# DIO_2.net
KiCad netlist of a schematic drawn in Altium Designer
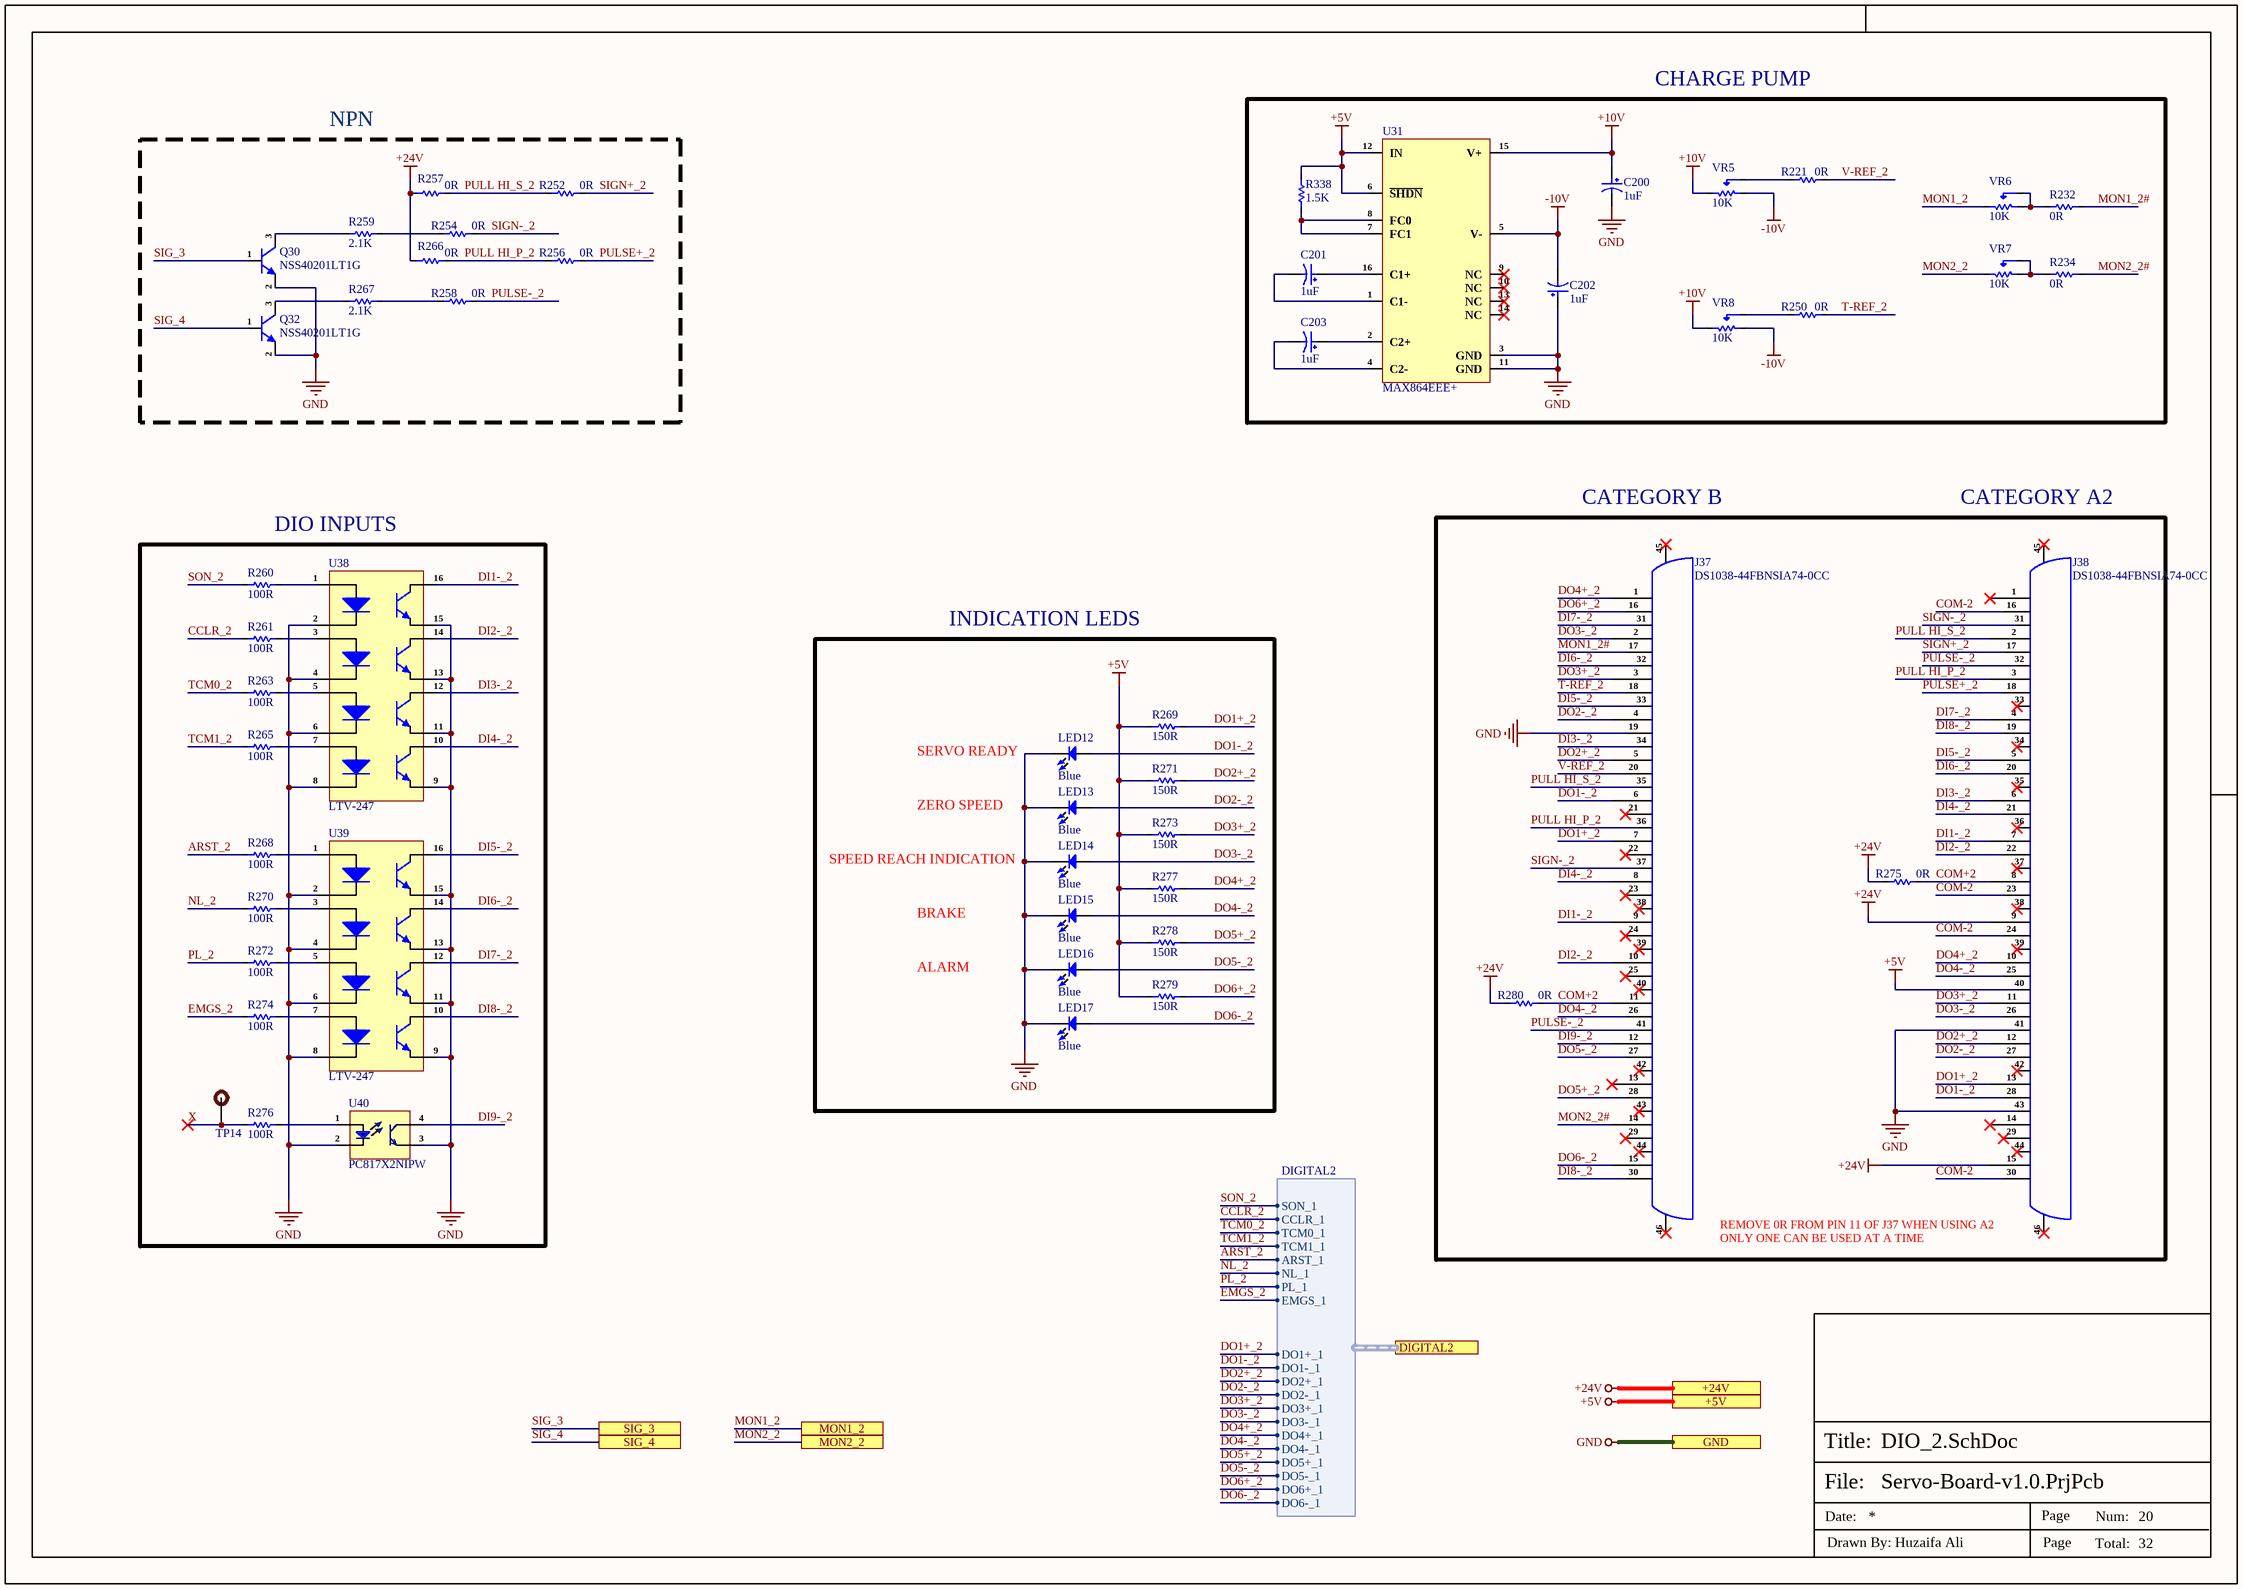
[diagram p0: DIO_2.SchDoc]

(export (version "E")
  (design (tool "Eeschema 10.0.6"))
  (components
    (comp (ref "C200")
      (value "1uF")
      (footprint "RVT1H1R0M0405")
      (description "1uF 50V 8mA@120Hz ±20% SMD,D4xL5.4mm Aluminum Electrolytic Capacitors - SMD ROHS")
      (fields (field (name "LCSC PART NUMBER") "C72491") (field (name "MANUFACTURER") "Roqang"))
      (libsource (lib "") (part "RVT1H1R0M0405_2"))
    )
    (comp (ref "C201")
      (value "1uF")
      (footprint "RVT1H1R0M0405")
      (description "1uF 50V 8mA@120Hz ±20% SMD,D4xL5.4mm Aluminum Electrolytic Capacitors - SMD ROHS")
      (fields (field (name "LCSC PART NUMBER") "C72491") (field (name "MANUFACTURER") "Roqang"))
      (libsource (lib "eSpark Libraries") (part "RVT1H1R0M0405"))
    )
    (comp (ref "C202")
      (value "1uF")
      (footprint "RVT1H1R0M0405")
      (description "1uF 50V 8mA@120Hz ±20% SMD,D4xL5.4mm Aluminum Electrolytic Capacitors - SMD ROHS")
      (fields (field (name "LCSC PART NUMBER") "C72491") (field (name "MANUFACTURER") "Roqang"))
      (libsource (lib "") (part "RVT1H1R0M0405_1"))
    )
    (comp (ref "C203")
      (value "1uF")
      (footprint "RVT1H1R0M0405")
      (description "1uF 50V 8mA@120Hz ±20% SMD,D4xL5.4mm Aluminum Electrolytic Capacitors - SMD ROHS")
      (fields (field (name "LCSC PART NUMBER") "C72491") (field (name "MANUFACTURER") "Roqang"))
      (libsource (lib "eSpark Libraries") (part "RVT1H1R0M0405"))
    )
    (comp (ref "J37")
      (value "DS1038-44FBNSIA74-0CC")
      (footprint "DS1038-44FBNSIA74-0CC")
      (description "44P Female D-Sub Right-Angle 3 1.5A -40℃~+105℃ Push-Pull D-Sub / VGA connector ROHS")
      (fields (field (name "MANUFACTURER") "CONNFLY Elec") (field (name "LCSC PART NUMBER") "C77844"))
      (libsource (lib "eSpark Libraries") (part "DS1038-44FBNSIA74-0CC"))
    )
    (comp (ref "J38")
      (value "DS1038-44FBNSIA74-0CC")
      (footprint "DS1038-44FBNSIA74-0CC")
      (description "44P Female D-Sub Right-Angle 3 1.5A -40℃~+105℃ Push-Pull D-Sub / VGA connector ROHS")
      (fields (field (name "MANUFACTURER") "CONNFLY Elec") (field (name "LCSC PART NUMBER") "C77844"))
      (libsource (lib "eSpark Libraries") (part "DS1038-44FBNSIA74-0CC"))
    )
    (comp (ref "LED12")
      (value "Blue")
      (footprint "LED-0603")
      (description "blue 0603 Light Emitting Diodes (LED) ROHS")
      (fields
        (field (name "MANUFACTURER") "Foshan NationStar Optoelectronics")
        (field (name "MANUFACTURER PART NUMBER") "NCD0603B3")
      )
      (libsource (lib "eSpark Libraries") (part "NCD0603B3"))
    )
    (comp (ref "LED13")
      (value "Blue")
      (footprint "LED-0603")
      (description "blue 0603 Light Emitting Diodes (LED) ROHS")
      (fields
        (field (name "MANUFACTURER") "Foshan NationStar Optoelectronics")
        (field (name "MANUFACTURER PART NUMBER") "NCD0603B3")
      )
      (libsource (lib "eSpark Libraries") (part "NCD0603B3"))
    )
    (comp (ref "LED14")
      (value "Blue")
      (footprint "LED-0603")
      (description "blue 0603 Light Emitting Diodes (LED) ROHS")
      (fields
        (field (name "MANUFACTURER") "Foshan NationStar Optoelectronics")
        (field (name "MANUFACTURER PART NUMBER") "NCD0603B3")
      )
      (libsource (lib "eSpark Libraries") (part "NCD0603B3"))
    )
    (comp (ref "LED15")
      (value "Blue")
      (footprint "LED-0603")
      (description "blue 0603 Light Emitting Diodes (LED) ROHS")
      (fields
        (field (name "MANUFACTURER") "Foshan NationStar Optoelectronics")
        (field (name "MANUFACTURER PART NUMBER") "NCD0603B3")
      )
      (libsource (lib "eSpark Libraries") (part "NCD0603B3"))
    )
    (comp (ref "LED16")
      (value "Blue")
      (footprint "LED-0603")
      (description "blue 0603 Light Emitting Diodes (LED) ROHS")
      (fields
        (field (name "MANUFACTURER") "Foshan NationStar Optoelectronics")
        (field (name "MANUFACTURER PART NUMBER") "NCD0603B3")
      )
      (libsource (lib "eSpark Libraries") (part "NCD0603B3"))
    )
    (comp (ref "LED17")
      (value "Blue")
      (footprint "LED-0603")
      (description "blue 0603 Light Emitting Diodes (LED) ROHS")
      (fields
        (field (name "MANUFACTURER") "Foshan NationStar Optoelectronics")
        (field (name "MANUFACTURER PART NUMBER") "NCD0603B3")
      )
      (libsource (lib "eSpark Libraries") (part "NCD0603B3"))
    )
    (comp (ref "Q30")
      (value "NSS40201LT1G")
      (footprint "SOT-23")
      (description "TRANS NPN 40V 2A SOT23-3")
      (fields (field (name "MANUFACTURER") "ON Semiconductor") (field (name "LCSC PART NUMBER") "C145175"))
      (libsource (lib "eSpark Libraries") (part "NSS40201LT1G"))
    )
    (comp (ref "Q32")
      (value "NSS40201LT1G")
      (footprint "SOT-23")
      (description "TRANS NPN 40V 2A SOT23-3")
      (fields (field (name "MANUFACTURER") "ON Semiconductor") (field (name "LCSC PART NUMBER") "C145175"))
      (libsource (lib "eSpark Libraries") (part "NSS40201LT1G"))
    )
    (comp (ref "R221")
      (value "0R")
      (footprint "Res-0402")
      (description "RES 0 OHM JUMPER 1/16W 0402")
      (fields
        (field (name "MANUFACTURER") "Yageo")
        (field (name "MANUFACTURER PART NUMBER") "RC0402FR-070RL")
      )
      (libsource (lib "eSpark Libraries") (part "RC0402FR-070RL"))
    )
    (comp (ref "R232")
      (value "0R")
      (footprint "Res-0402")
      (description "RES 0 OHM JUMPER 1/16W 0402")
      (fields
        (field (name "MANUFACTURER") "Yageo")
        (field (name "MANUFACTURER PART NUMBER") "RC0402FR-070RL")
      )
      (libsource (lib "eSpark Libraries") (part "RC0402FR-070RL"))
    )
    (comp (ref "R234")
      (value "0R")
      (footprint "Res-0402")
      (description "RES 0 OHM JUMPER 1/16W 0402")
      (fields
        (field (name "MANUFACTURER") "Yageo")
        (field (name "MANUFACTURER PART NUMBER") "RC0402FR-070RL")
      )
      (libsource (lib "eSpark Libraries") (part "RC0402FR-070RL"))
    )
    (comp (ref "R250")
      (value "0R")
      (footprint "Res-0402")
      (description "RES 0 OHM JUMPER 1/16W 0402")
      (fields
        (field (name "MANUFACTURER") "Yageo")
        (field (name "MANUFACTURER PART NUMBER") "RC0402FR-070RL")
      )
      (libsource (lib "eSpark Libraries") (part "RC0402FR-070RL"))
    )
    (comp (ref "R252")
      (value "0R")
      (footprint "Res-0603")
      (description "RES 0 OHM JUMPER 1/10W 0603")
      (fields
        (field (name "MANUFACTURER") "Yageo")
        (field (name "MANUFACTURER PART NUMBER") "RC0603JR-070RL")
      )
      (libsource (lib "eSpark Libraries") (part "RC0603JR-070RL"))
    )
    (comp (ref "R254")
      (value "0R")
      (footprint "Res-0603")
      (description "RES 0 OHM JUMPER 1/10W 0603")
      (fields
        (field (name "MANUFACTURER") "Yageo")
        (field (name "MANUFACTURER PART NUMBER") "RC0603JR-070RL")
      )
      (libsource (lib "eSpark Libraries") (part "RC0603JR-070RL"))
    )
    (comp (ref "R256")
      (value "0R")
      (footprint "Res-0603")
      (description "RES 0 OHM JUMPER 1/10W 0603")
      (fields
        (field (name "MANUFACTURER") "Yageo")
        (field (name "MANUFACTURER PART NUMBER") "RC0603JR-070RL")
      )
      (libsource (lib "eSpark Libraries") (part "RC0603JR-070RL"))
    )
    (comp (ref "R257")
      (value "0R")
      (footprint "Res-0603")
      (description "RES 0 OHM JUMPER 1/10W 0603")
      (fields
        (field (name "MANUFACTURER") "Yageo")
        (field (name "MANUFACTURER PART NUMBER") "RC0603JR-070RL")
      )
      (libsource (lib "eSpark Libraries") (part "RC0603JR-070RL"))
    )
    (comp (ref "R258")
      (value "0R")
      (footprint "Res-0603")
      (description "RES 0 OHM JUMPER 1/10W 0603")
      (fields
        (field (name "MANUFACTURER") "Yageo")
        (field (name "MANUFACTURER PART NUMBER") "RC0603JR-070RL")
      )
      (libsource (lib "eSpark Libraries") (part "RC0603JR-070RL"))
    )
    (comp (ref "R259")
      (value "2.1K")
      (footprint "Res-0603")
      (description "RES SMD 2.1K OHM 0.1% 1/10W 0603")
      (fields
        (field (name "MANUFACTURER") "Yageo")
        (field (name "MANUFACTURER PART NUMBER") "RT0603BRD072K1L")
      )
      (libsource (lib "eSpark Libraries") (part "RT0603BRD072K1L"))
    )
    (comp (ref "R260")
      (value "100R")
      (footprint "Res-0402")
      (description "RES 100 OHM 1% 1/16W 0402")
      (fields
        (field (name "MANUFACTURER") "Yageo")
        (field (name "MANUFACTURER PART NUMBER") "RC0402FR-07100RL")
      )
      (libsource (lib "eSpark Libraries") (part "RC0402FR-07100RL"))
    )
    (comp (ref "R261")
      (value "100R")
      (footprint "Res-0402")
      (description "RES 100 OHM 1% 1/16W 0402")
      (fields
        (field (name "MANUFACTURER") "Yageo")
        (field (name "MANUFACTURER PART NUMBER") "RC0402FR-07100RL")
      )
      (libsource (lib "eSpark Libraries") (part "RC0402FR-07100RL"))
    )
    (comp (ref "R263")
      (value "100R")
      (footprint "Res-0402")
      (description "RES 100 OHM 1% 1/16W 0402")
      (fields
        (field (name "MANUFACTURER") "Yageo")
        (field (name "MANUFACTURER PART NUMBER") "RC0402FR-07100RL")
      )
      (libsource (lib "eSpark Libraries") (part "RC0402FR-07100RL"))
    )
    (comp (ref "R265")
      (value "100R")
      (footprint "Res-0402")
      (description "RES 100 OHM 1% 1/16W 0402")
      (fields
        (field (name "MANUFACTURER") "Yageo")
        (field (name "MANUFACTURER PART NUMBER") "RC0402FR-07100RL")
      )
      (libsource (lib "eSpark Libraries") (part "RC0402FR-07100RL"))
    )
    (comp (ref "R266")
      (value "0R")
      (footprint "Res-0603")
      (description "RES 0 OHM JUMPER 1/10W 0603")
      (fields
        (field (name "MANUFACTURER") "Yageo")
        (field (name "MANUFACTURER PART NUMBER") "RC0603JR-070RL")
      )
      (libsource (lib "eSpark Libraries") (part "RC0603JR-070RL"))
    )
    (comp (ref "R267")
      (value "2.1K")
      (footprint "Res-0603")
      (description "RES SMD 2.1K OHM 0.1% 1/10W 0603")
      (fields
        (field (name "MANUFACTURER") "Yageo")
        (field (name "MANUFACTURER PART NUMBER") "RT0603BRD072K1L")
      )
      (libsource (lib "eSpark Libraries") (part "RT0603BRD072K1L"))
    )
    (comp (ref "R268")
      (value "100R")
      (footprint "Res-0402")
      (description "RES 100 OHM 1% 1/16W 0402")
      (fields
        (field (name "MANUFACTURER") "Yageo")
        (field (name "MANUFACTURER PART NUMBER") "RC0402FR-07100RL")
      )
      (libsource (lib "eSpark Libraries") (part "RC0402FR-07100RL"))
    )
    (comp (ref "R269")
      (value "150R")
      (footprint "Res-0603")
      (description "RES 150 OHM 0.5% 1/10W 0603")
      (fields
        (field (name "MANUFACTURER") "Yageo")
        (field (name "MANUFACTURER PART NUMBER") "RC0603DR-07150RL")
      )
      (libsource (lib "eSpark Libraries") (part "RC0603DR-07150RL"))
    )
    (comp (ref "R270")
      (value "100R")
      (footprint "Res-0402")
      (description "RES 100 OHM 1% 1/16W 0402")
      (fields
        (field (name "MANUFACTURER") "Yageo")
        (field (name "MANUFACTURER PART NUMBER") "RC0402FR-07100RL")
      )
      (libsource (lib "eSpark Libraries") (part "RC0402FR-07100RL"))
    )
    (comp (ref "R271")
      (value "150R")
      (footprint "Res-0603")
      (description "RES 150 OHM 0.5% 1/10W 0603")
      (fields
        (field (name "MANUFACTURER") "Yageo")
        (field (name "MANUFACTURER PART NUMBER") "RC0603DR-07150RL")
      )
      (libsource (lib "eSpark Libraries") (part "RC0603DR-07150RL"))
    )
    (comp (ref "R272")
      (value "100R")
      (footprint "Res-0402")
      (description "RES 100 OHM 1% 1/16W 0402")
      (fields
        (field (name "MANUFACTURER") "Yageo")
        (field (name "MANUFACTURER PART NUMBER") "RC0402FR-07100RL")
      )
      (libsource (lib "eSpark Libraries") (part "RC0402FR-07100RL"))
    )
    (comp (ref "R273")
      (value "150R")
      (footprint "Res-0603")
      (description "RES 150 OHM 0.5% 1/10W 0603")
      (fields
        (field (name "MANUFACTURER") "Yageo")
        (field (name "MANUFACTURER PART NUMBER") "RC0603DR-07150RL")
      )
      (libsource (lib "eSpark Libraries") (part "RC0603DR-07150RL"))
    )
    (comp (ref "R274")
      (value "100R")
      (footprint "Res-0402")
      (description "RES 100 OHM 1% 1/16W 0402")
      (fields
        (field (name "MANUFACTURER") "Yageo")
        (field (name "MANUFACTURER PART NUMBER") "RC0402FR-07100RL")
      )
      (libsource (lib "eSpark Libraries") (part "RC0402FR-07100RL"))
    )
    (comp (ref "R275")
      (value "0R")
      (footprint "Res-0402")
      (description "RES 0 OHM JUMPER 1/16W 0402")
      (fields
        (field (name "MANUFACTURER") "Yageo")
        (field (name "MANUFACTURER PART NUMBER") "RC0402FR-070RL")
      )
      (libsource (lib "eSpark Libraries") (part "RC0402FR-070RL"))
    )
    (comp (ref "R276")
      (value "100R")
      (footprint "Res-0402")
      (description "RES 100 OHM 1% 1/16W 0402")
      (fields
        (field (name "MANUFACTURER") "Yageo")
        (field (name "MANUFACTURER PART NUMBER") "RC0402FR-07100RL")
      )
      (libsource (lib "eSpark Libraries") (part "RC0402FR-07100RL"))
    )
    (comp (ref "R277")
      (value "150R")
      (footprint "Res-0603")
      (description "RES 150 OHM 0.5% 1/10W 0603")
      (fields
        (field (name "MANUFACTURER") "Yageo")
        (field (name "MANUFACTURER PART NUMBER") "RC0603DR-07150RL")
      )
      (libsource (lib "eSpark Libraries") (part "RC0603DR-07150RL"))
    )
    (comp (ref "R278")
      (value "150R")
      (footprint "Res-0603")
      (description "RES 150 OHM 0.5% 1/10W 0603")
      (fields
        (field (name "MANUFACTURER") "Yageo")
        (field (name "MANUFACTURER PART NUMBER") "RC0603DR-07150RL")
      )
      (libsource (lib "eSpark Libraries") (part "RC0603DR-07150RL"))
    )
    (comp (ref "R279")
      (value "150R")
      (footprint "Res-0603")
      (description "RES 150 OHM 0.5% 1/10W 0603")
      (fields
        (field (name "MANUFACTURER") "Yageo")
        (field (name "MANUFACTURER PART NUMBER") "RC0603DR-07150RL")
      )
      (libsource (lib "eSpark Libraries") (part "RC0603DR-07150RL"))
    )
    (comp (ref "R280")
      (value "0R")
      (footprint "Res-0402")
      (description "RES 0 OHM JUMPER 1/16W 0402")
      (fields
        (field (name "MANUFACTURER") "Yageo")
        (field (name "MANUFACTURER PART NUMBER") "RC0402FR-070RL")
      )
      (libsource (lib "eSpark Libraries") (part "RC0402FR-070RL"))
    )
    (comp (ref "R338")
      (value "1.5K")
      (footprint "Res-0402")
      (description "RES 1.5K OHM 1% 1/16W 0402")
      (fields
        (field (name "MANUFACTURER") "Yageo")
        (field (name "MANUFACTURER PART NUMBER") "RC0402FR-071K5L")
      )
      (libsource (lib "eSpark Libraries") (part "RC0402FR-071K5L"))
    )
    (comp (ref "TP14")
      (value "TEST POINT")
      (footprint "Test-point")
      (description "Test Point ON")
      (libsource (lib "eSpark Libraries") (part "TEST POINT"))
    )
    (comp (ref "U31")
      (value "MAX864EEE+")
      (footprint "16-QSOP")
      (description "IC REG CHARGE PUMP INV 16QSOP")
      (fields (field (name "MANUFACTURER") "Maxim"))
      (libsource (lib "eSpark Libraries") (part "MAX864EEE+"))
    )
    (comp (ref "U38")
      (value "LTV-247")
      (footprint "16-SO")
      (description "OPTOISO 3.75KV 4CH TRANS 16SO")
      (fields (field (name "MANUFACTURER") "Vishay Lite-On") (field (name "LCSC PART NUMBER") "C115451"))
      (libsource (lib "eSpark Libraries") (part "LTV-247"))
    )
    (comp (ref "U39")
      (value "LTV-247")
      (footprint "16-SO")
      (description "OPTOISO 3.75KV 4CH TRANS 16SO")
      (fields (field (name "MANUFACTURER") "Vishay Lite-On") (field (name "LCSC PART NUMBER") "C115451"))
      (libsource (lib "eSpark Libraries") (part "LTV-247"))
    )
    (comp (ref "U40")
      (value "PC817X2NIPW")
      (footprint "PC817X2NIPW")
      (description "Optoisolator Output Channel 4-SMD")
      (fields (field (name "MANUFACTURER") "Sharp") (field (name "LCSC PART NUMBER") "C2840443"))
      (libsource (lib "eSpark Libraries") (part "PC817X2NIPW"))
    )
    (comp (ref "VR5")
      (value "10K")
      (footprint "3362P-1-103")
      (description "TRIMMER 10K OHM 0.5W PC PIN TOP")
      (fields (field (name "LCSC PART NUMBER") "C118956") (field (name "MANUFACTURER") "Bourns"))
      (libsource (lib "eSpark Libraries") (part "3362P-1-103"))
    )
    (comp (ref "VR6")
      (value "10K")
      (footprint "3362P-1-103")
      (description "TRIMMER 10K OHM 0.5W PC PIN TOP")
      (fields (field (name "LCSC PART NUMBER") "C118956") (field (name "MANUFACTURER") "Bourns"))
      (libsource (lib "eSpark Libraries") (part "3362P-1-103"))
    )
    (comp (ref "VR7")
      (value "10K")
      (footprint "3362P-1-103")
      (description "TRIMMER 10K OHM 0.5W PC PIN TOP")
      (fields (field (name "LCSC PART NUMBER") "C118956") (field (name "MANUFACTURER") "Bourns"))
      (libsource (lib "eSpark Libraries") (part "3362P-1-103"))
    )
    (comp (ref "VR8")
      (value "10K")
      (footprint "3362P-1-103")
      (description "TRIMMER 10K OHM 0.5W PC PIN TOP")
      (fields (field (name "LCSC PART NUMBER") "C118956") (field (name "MANUFACTURER") "Bourns"))
      (libsource (lib "eSpark Libraries") (part "3362P-1-103"))
    )
  )
  (nets
    (net (code "2") (name "+5V") (class "Default")
      (node (ref "J38") (pin "40") (pinfunction "40_40") (pintype "passive"))
      (node (ref "R269") (pin "1") (pinfunction "1_1") (pintype "passive"))
      (node (ref "R271") (pin "1") (pinfunction "1_1") (pintype "passive"))
      (node (ref "R273") (pin "1") (pinfunction "1_1") (pintype "passive"))
      (node (ref "R277") (pin "1") (pinfunction "1_1") (pintype "passive"))
      (node (ref "R278") (pin "1") (pinfunction "1_1") (pintype "passive"))
      (node (ref "R279") (pin "1") (pinfunction "1_1") (pintype "passive"))
      (node (ref "R338") (pin "2") (pinfunction "2_2") (pintype "passive"))
      (node (ref "U31") (pin "12") (pinfunction "IN_12") (pintype "passive"))
      (node (ref "U31") (pin "6") (pinfunction "~{SHDN}_6") (pintype "passive"))
    )
    (net (code "3") (name "+10V") (class "Default")
      (node (ref "C200") (pin "1") (pintype "passive"))
      (node (ref "U31") (pin "15") (pinfunction "V+_15") (pintype "passive"))
      (node (ref "VR5") (pin "3") (pinfunction "CW_3") (pintype "passive"))
      (node (ref "VR8") (pin "3") (pinfunction "CW_3") (pintype "passive"))
    )
    (net (code "4") (name "+24V") (class "Default")
      (node (ref "J38") (pin "15") (pinfunction "15_15") (pintype "passive"))
      (node (ref "J38") (pin "9") (pinfunction "9_9") (pintype "passive"))
      (node (ref "R257") (pin "1") (pinfunction "1_1") (pintype "passive"))
      (node (ref "R266") (pin "1") (pinfunction "1_1") (pintype "passive"))
      (node (ref "R275") (pin "1") (pinfunction "1_1") (pintype "passive"))
      (node (ref "R280") (pin "1") (pinfunction "1_1") (pintype "passive"))
    )
    (net (code "5") (name "-10V") (class "Default")
      (node (ref "C202") (pin "2") (pintype "passive"))
      (node (ref "U31") (pin "5") (pinfunction "V-_5") (pintype "passive"))
      (node (ref "VR5") (pin "1") (pinfunction "CCW_1") (pintype "passive"))
      (node (ref "VR8") (pin "1") (pinfunction "CCW_1") (pintype "passive"))
    )
    (net (code "6") (name "/ARST_2") (class "Default")
      (node (ref "R268") (pin "1") (pinfunction "1_1") (pintype "passive"))
    )
    (net (code "7") (name "/CCLR_2") (class "Default")
      (node (ref "R261") (pin "1") (pinfunction "1_1") (pintype "passive"))
    )
    (net (code "8") (name "/COM+2") (class "Default")
      (node (ref "J37") (pin "11") (pinfunction "11_11") (pintype "passive"))
      (node (ref "J38") (pin "8") (pinfunction "8_8") (pintype "passive"))
      (node (ref "R275") (pin "2") (pinfunction "2_2") (pintype "passive"))
      (node (ref "R280") (pin "2") (pinfunction "2_2") (pintype "passive"))
    )
    (net (code "9") (name "/COM-2") (class "Default")
      (node (ref "J38") (pin "16") (pinfunction "16_16") (pintype "passive"))
      (node (ref "J38") (pin "23") (pinfunction "23_23") (pintype "passive"))
      (node (ref "J38") (pin "24") (pinfunction "24_24") (pintype "passive"))
      (node (ref "J38") (pin "30") (pinfunction "30_30") (pintype "passive"))
    )
    (net (code "10") (name "/DI1-_2") (class "Default")
      (node (ref "J37") (pin "9") (pinfunction "9_9") (pintype "passive"))
      (node (ref "J38") (pin "7") (pinfunction "7_7") (pintype "passive"))
      (node (ref "U38") (pin "16") (pinfunction "C_16") (pintype "passive"))
    )
    (net (code "11") (name "/DI2-_2") (class "Default")
      (node (ref "J37") (pin "10") (pinfunction "10_10") (pintype "passive"))
      (node (ref "J38") (pin "22") (pinfunction "22_22") (pintype "passive"))
      (node (ref "U38") (pin "14") (pinfunction "C_14") (pintype "passive"))
    )
    (net (code "12") (name "/DI3-_2") (class "Default")
      (node (ref "J37") (pin "34") (pinfunction "34_34") (pintype "passive"))
      (node (ref "J38") (pin "6") (pinfunction "6_6") (pintype "passive"))
      (node (ref "U38") (pin "12") (pinfunction "C_12") (pintype "passive"))
    )
    (net (code "13") (name "/DI4-_2") (class "Default")
      (node (ref "J37") (pin "8") (pinfunction "8_8") (pintype "passive"))
      (node (ref "J38") (pin "21") (pinfunction "21_21") (pintype "passive"))
      (node (ref "U38") (pin "10") (pinfunction "C_10") (pintype "passive"))
    )
    (net (code "14") (name "/DI5-_2") (class "Default")
      (node (ref "J37") (pin "33") (pinfunction "33_33") (pintype "passive"))
      (node (ref "J38") (pin "5") (pinfunction "5_5") (pintype "passive"))
      (node (ref "U39") (pin "16") (pinfunction "C_16") (pintype "passive"))
    )
    (net (code "15") (name "/DI6-_2") (class "Default")
      (node (ref "J37") (pin "32") (pinfunction "32_32") (pintype "passive"))
      (node (ref "J38") (pin "20") (pinfunction "20_20") (pintype "passive"))
      (node (ref "U39") (pin "14") (pinfunction "C_14") (pintype "passive"))
    )
    (net (code "16") (name "/DI7-_2") (class "Default")
      (node (ref "J37") (pin "31") (pinfunction "31_31") (pintype "passive"))
      (node (ref "J38") (pin "4") (pinfunction "4_4") (pintype "passive"))
      (node (ref "U39") (pin "12") (pinfunction "C_12") (pintype "passive"))
    )
    (net (code "17") (name "/DI8-_2") (class "Default")
      (node (ref "J37") (pin "30") (pinfunction "30_30") (pintype "passive"))
      (node (ref "J38") (pin "19") (pinfunction "19_19") (pintype "passive"))
      (node (ref "U39") (pin "10") (pinfunction "C_10") (pintype "passive"))
    )
    (net (code "18") (name "/DI9-_2") (class "Default")
      (node (ref "J37") (pin "12") (pinfunction "12_12") (pintype "passive"))
      (node (ref "U40") (pin "4") (pinfunction "C_4") (pintype "passive"))
    )
    (net (code "19") (name "/DO1+_2") (class "Default")
      (node (ref "J37") (pin "7") (pinfunction "7_7") (pintype "passive"))
      (node (ref "J38") (pin "13") (pinfunction "13_13") (pintype "passive"))
      (node (ref "R269") (pin "2") (pinfunction "2_2") (pintype "passive"))
    )
    (net (code "20") (name "/DO1-_2") (class "Default")
      (node (ref "J37") (pin "6") (pinfunction "6_6") (pintype "passive"))
      (node (ref "J38") (pin "28") (pinfunction "28_28") (pintype "passive"))
      (node (ref "LED12") (pin "1") (pinfunction "1_1") (pintype "passive"))
    )
    (net (code "21") (name "/DO2+_2") (class "Default")
      (node (ref "J37") (pin "5") (pinfunction "5_5") (pintype "passive"))
      (node (ref "J38") (pin "12") (pinfunction "12_12") (pintype "passive"))
      (node (ref "R271") (pin "2") (pinfunction "2_2") (pintype "passive"))
    )
    (net (code "22") (name "/DO2-_2") (class "Default")
      (node (ref "J37") (pin "4") (pinfunction "4_4") (pintype "passive"))
      (node (ref "J38") (pin "27") (pinfunction "27_27") (pintype "passive"))
      (node (ref "LED13") (pin "1") (pinfunction "1_1") (pintype "passive"))
    )
    (net (code "23") (name "/DO3+_2") (class "Default")
      (node (ref "J37") (pin "3") (pinfunction "3_3") (pintype "passive"))
      (node (ref "J38") (pin "11") (pinfunction "11_11") (pintype "passive"))
      (node (ref "R273") (pin "2") (pinfunction "2_2") (pintype "passive"))
    )
    (net (code "24") (name "/DO3-_2") (class "Default")
      (node (ref "J37") (pin "2") (pinfunction "2_2") (pintype "passive"))
      (node (ref "J38") (pin "26") (pinfunction "26_26") (pintype "passive"))
      (node (ref "LED14") (pin "1") (pinfunction "1_1") (pintype "passive"))
    )
    (net (code "25") (name "/DO4+_2") (class "Default")
      (node (ref "J37") (pin "1") (pinfunction "1_1") (pintype "passive"))
      (node (ref "J38") (pin "10") (pinfunction "10_10") (pintype "passive"))
      (node (ref "R277") (pin "2") (pinfunction "2_2") (pintype "passive"))
    )
    (net (code "26") (name "/DO4-_2") (class "Default")
      (node (ref "J37") (pin "26") (pinfunction "26_26") (pintype "passive"))
      (node (ref "J38") (pin "25") (pinfunction "25_25") (pintype "passive"))
      (node (ref "LED15") (pin "1") (pinfunction "1_1") (pintype "passive"))
    )
    (net (code "27") (name "/DO5+_2") (class "Default")
      (node (ref "J37") (pin "28") (pinfunction "28_28") (pintype "passive"))
      (node (ref "R278") (pin "2") (pinfunction "2_2") (pintype "passive"))
    )
    (net (code "28") (name "/DO5-_2") (class "Default")
      (node (ref "J37") (pin "27") (pinfunction "27_27") (pintype "passive"))
      (node (ref "LED16") (pin "1") (pinfunction "1_1") (pintype "passive"))
    )
    (net (code "29") (name "/DO6+_2") (class "Default")
      (node (ref "J37") (pin "16") (pinfunction "16_16") (pintype "passive"))
      (node (ref "R279") (pin "2") (pinfunction "2_2") (pintype "passive"))
    )
    (net (code "30") (name "/DO6-_2") (class "Default")
      (node (ref "J37") (pin "15") (pinfunction "15_15") (pintype "passive"))
      (node (ref "LED17") (pin "1") (pinfunction "1_1") (pintype "passive"))
    )
    (net (code "31") (name "/EMGS_2") (class "Default")
      (node (ref "R274") (pin "1") (pinfunction "1_1") (pintype "passive"))
    )
    (net (code "32") (name "/MON1_2") (class "Default")
      (node (ref "VR6") (pin "3") (pinfunction "CW_3") (pintype "passive"))
    )
    (net (code "33") (name "/MON1_2#") (class "Default")
      (node (ref "J37") (pin "17") (pinfunction "17_17") (pintype "passive"))
      (node (ref "R232") (pin "2") (pinfunction "2_2") (pintype "passive"))
    )
    (net (code "34") (name "/MON2_2") (class "Default")
      (node (ref "VR7") (pin "3") (pinfunction "CW_3") (pintype "passive"))
    )
    (net (code "35") (name "/MON2_2#") (class "Default")
      (node (ref "J37") (pin "14") (pinfunction "14_14") (pintype "passive"))
      (node (ref "R234") (pin "2") (pinfunction "2_2") (pintype "passive"))
    )
    (net (code "36") (name "/NL_2") (class "Default")
      (node (ref "R270") (pin "1") (pinfunction "1_1") (pintype "passive"))
    )
    (net (code "37") (name "/PL_2") (class "Default")
      (node (ref "R272") (pin "1") (pinfunction "1_1") (pintype "passive"))
    )
    (net (code "38") (name "/PULL HI_P_2") (class "Default")
      (node (ref "J37") (pin "36") (pinfunction "36_36") (pintype "passive"))
      (node (ref "J38") (pin "3") (pinfunction "3_3") (pintype "passive"))
      (node (ref "R256") (pin "1") (pinfunction "1_1") (pintype "passive"))
      (node (ref "R266") (pin "2") (pinfunction "2_2") (pintype "passive"))
    )
    (net (code "39") (name "/PULL HI_S_2") (class "Default")
      (node (ref "J37") (pin "35") (pinfunction "35_35") (pintype "passive"))
      (node (ref "J38") (pin "2") (pinfunction "2_2") (pintype "passive"))
      (node (ref "R252") (pin "1") (pinfunction "1_1") (pintype "passive"))
      (node (ref "R257") (pin "2") (pinfunction "2_2") (pintype "passive"))
    )
    (net (code "40") (name "/PULSE+_2") (class "Default")
      (node (ref "J38") (pin "18") (pinfunction "18_18") (pintype "passive"))
      (node (ref "R256") (pin "2") (pinfunction "2_2") (pintype "passive"))
    )
    (net (code "41") (name "/PULSE-_2") (class "Default")
      (node (ref "J37") (pin "41") (pinfunction "41_41") (pintype "passive"))
      (node (ref "J38") (pin "32") (pinfunction "32_32") (pintype "passive"))
      (node (ref "R258") (pin "2") (pinfunction "2_2") (pintype "passive"))
    )
    (net (code "42") (name "/SIGN+_2") (class "Default")
      (node (ref "J38") (pin "17") (pinfunction "17_17") (pintype "passive"))
      (node (ref "R252") (pin "2") (pinfunction "2_2") (pintype "passive"))
    )
    (net (code "43") (name "/SIGN-_2") (class "Default")
      (node (ref "J37") (pin "37") (pinfunction "37_37") (pintype "passive"))
      (node (ref "J38") (pin "31") (pinfunction "31_31") (pintype "passive"))
      (node (ref "R254") (pin "2") (pinfunction "2_2") (pintype "passive"))
    )
    (net (code "44") (name "/SIG_3") (class "Default")
      (node (ref "Q30") (pin "1") (pinfunction "B_1") (pintype "passive"))
    )
    (net (code "45") (name "/SIG_4") (class "Default")
      (node (ref "Q32") (pin "1") (pinfunction "B_1") (pintype "passive"))
    )
    (net (code "46") (name "/SON_2") (class "Default")
      (node (ref "R260") (pin "1") (pinfunction "1_1") (pintype "passive"))
    )
    (net (code "47") (name "/T-REF_2") (class "Default")
      (node (ref "J37") (pin "18") (pinfunction "18_18") (pintype "passive"))
      (node (ref "R250") (pin "2") (pinfunction "2_2") (pintype "passive"))
    )
    (net (code "48") (name "/TCM0_2") (class "Default")
      (node (ref "R263") (pin "1") (pinfunction "1_1") (pintype "passive"))
    )
    (net (code "49") (name "/TCM1_2") (class "Default")
      (node (ref "R265") (pin "1") (pinfunction "1_1") (pintype "passive"))
    )
    (net (code "50") (name "/V-REF_2") (class "Default")
      (node (ref "J37") (pin "20") (pinfunction "20_20") (pintype "passive"))
      (node (ref "R221") (pin "2") (pinfunction "2_2") (pintype "passive"))
    )
    (net (code "51") (name "/X") (class "Default")
      (node (ref "R276") (pin "1") (pinfunction "1_1") (pintype "passive"))
      (node (ref "TP14") (pin "1") (pinfunction "1_1") (pintype "passive"))
    )
    (net (code "53") (name "GND") (class "Default")
      (node (ref "C200") (pin "2") (pintype "passive"))
      (node (ref "C202") (pin "1") (pintype "passive"))
      (node (ref "J37") (pin "19") (pinfunction "19_19") (pintype "passive"))
      (node (ref "J38") (pin "41") (pinfunction "41_41") (pintype "passive"))
      (node (ref "J38") (pin "43") (pinfunction "43_43") (pintype "passive"))
      (node (ref "LED12") (pin "2") (pinfunction "2_2") (pintype "passive"))
      (node (ref "LED13") (pin "2") (pinfunction "2_2") (pintype "passive"))
      (node (ref "LED14") (pin "2") (pinfunction "2_2") (pintype "passive"))
      (node (ref "LED15") (pin "2") (pinfunction "2_2") (pintype "passive"))
      (node (ref "LED16") (pin "2") (pinfunction "2_2") (pintype "passive"))
      (node (ref "LED17") (pin "2") (pinfunction "2_2") (pintype "passive"))
      (node (ref "Q30") (pin "2") (pinfunction "E_2") (pintype "passive"))
      (node (ref "Q32") (pin "2") (pinfunction "E_2") (pintype "passive"))
      (node (ref "U31") (pin "11") (pinfunction "GND_11") (pintype "passive"))
      (node (ref "U31") (pin "3") (pinfunction "GND_3") (pintype "passive"))
      (node (ref "U38") (pin "11") (pinfunction "E_11") (pintype "passive"))
      (node (ref "U38") (pin "13") (pinfunction "E_13") (pintype "passive"))
      (node (ref "U38") (pin "15") (pinfunction "E_15") (pintype "passive"))
      (node (ref "U38") (pin "2") (pinfunction "K_2") (pintype "passive"))
      (node (ref "U38") (pin "4") (pinfunction "K_4") (pintype "passive"))
      (node (ref "U38") (pin "6") (pinfunction "K_6") (pintype "passive"))
      (node (ref "U38") (pin "8") (pinfunction "K_8") (pintype "passive"))
      (node (ref "U38") (pin "9") (pinfunction "E_9") (pintype "passive"))
      (node (ref "U39") (pin "11") (pinfunction "E_11") (pintype "passive"))
      (node (ref "U39") (pin "13") (pinfunction "E_13") (pintype "passive"))
      (node (ref "U39") (pin "15") (pinfunction "E_15") (pintype "passive"))
      (node (ref "U39") (pin "2") (pinfunction "K_2") (pintype "passive"))
      (node (ref "U39") (pin "4") (pinfunction "K_4") (pintype "passive"))
      (node (ref "U39") (pin "6") (pinfunction "K_6") (pintype "passive"))
      (node (ref "U39") (pin "8") (pinfunction "K_8") (pintype "passive"))
      (node (ref "U39") (pin "9") (pinfunction "E_9") (pintype "passive"))
      (node (ref "U40") (pin "2") (pinfunction "Ca_2") (pintype "passive"))
      (node (ref "U40") (pin "3") (pinfunction "E_3") (pintype "passive"))
    )
    (net (code "54") (name "Net-(Q30-C)") (class "Default")
      (node (ref "Q30") (pin "3") (pinfunction "C_3") (pintype "passive"))
      (node (ref "R259") (pin "1") (pinfunction "1_1") (pintype "passive"))
    )
    (net (code "55") (name "Net-(Q32-C)") (class "Default")
      (node (ref "Q32") (pin "3") (pinfunction "C_3") (pintype "passive"))
      (node (ref "R267") (pin "1") (pinfunction "1_1") (pintype "passive"))
    )
    (net (code "56") (name "Net-(R254-Pad1)") (class "Default")
      (node (ref "R254") (pin "1") (pinfunction "1_1") (pintype "passive"))
      (node (ref "R259") (pin "2") (pinfunction "2_2") (pintype "passive"))
    )
    (net (code "57") (name "Net-(R258-Pad1)") (class "Default")
      (node (ref "R258") (pin "1") (pinfunction "1_1") (pintype "passive"))
      (node (ref "R267") (pin "2") (pinfunction "2_2") (pintype "passive"))
    )
    (net (code "58") (name "Net-(R260-Pad2)") (class "Default")
      (node (ref "R260") (pin "2") (pinfunction "2_2") (pintype "passive"))
      (node (ref "U38") (pin "1") (pinfunction "A_1") (pintype "passive"))
    )
    (net (code "59") (name "Net-(R261-Pad2)") (class "Default")
      (node (ref "R261") (pin "2") (pinfunction "2_2") (pintype "passive"))
      (node (ref "U38") (pin "3") (pinfunction "A_3") (pintype "passive"))
    )
    (net (code "60") (name "Net-(R263-Pad2)") (class "Default")
      (node (ref "R263") (pin "2") (pinfunction "2_2") (pintype "passive"))
      (node (ref "U38") (pin "5") (pinfunction "A_5") (pintype "passive"))
    )
    (net (code "61") (name "Net-(R265-Pad2)") (class "Default")
      (node (ref "R265") (pin "2") (pinfunction "2_2") (pintype "passive"))
      (node (ref "U38") (pin "7") (pinfunction "A_7") (pintype "passive"))
    )
    (net (code "62") (name "Net-(R268-Pad2)") (class "Default")
      (node (ref "R268") (pin "2") (pinfunction "2_2") (pintype "passive"))
      (node (ref "U39") (pin "1") (pinfunction "A_1") (pintype "passive"))
    )
    (net (code "63") (name "Net-(R270-Pad2)") (class "Default")
      (node (ref "R270") (pin "2") (pinfunction "2_2") (pintype "passive"))
      (node (ref "U39") (pin "3") (pinfunction "A_3") (pintype "passive"))
    )
    (net (code "64") (name "Net-(R272-Pad2)") (class "Default")
      (node (ref "R272") (pin "2") (pinfunction "2_2") (pintype "passive"))
      (node (ref "U39") (pin "5") (pinfunction "A_5") (pintype "passive"))
    )
    (net (code "65") (name "Net-(R274-Pad2)") (class "Default")
      (node (ref "R274") (pin "2") (pinfunction "2_2") (pintype "passive"))
      (node (ref "U39") (pin "7") (pinfunction "A_7") (pintype "passive"))
    )
    (net (code "66") (name "Net-(U31-C1+)") (class "Default")
      (node (ref "C201") (pin "1") (pintype "passive"))
      (node (ref "U31") (pin "16") (pinfunction "C1+_16") (pintype "passive"))
    )
    (net (code "67") (name "Net-(U31-C1-)") (class "Default")
      (node (ref "C201") (pin "2") (pintype "passive"))
      (node (ref "U31") (pin "1") (pinfunction "C1-_1") (pintype "passive"))
    )
    (net (code "68") (name "Net-(U31-C2+)") (class "Default")
      (node (ref "C203") (pin "1") (pintype "passive"))
      (node (ref "U31") (pin "2") (pinfunction "C2+_2") (pintype "passive"))
    )
    (net (code "69") (name "Net-(U31-C2-)") (class "Default")
      (node (ref "C203") (pin "2") (pintype "passive"))
      (node (ref "U31") (pin "4") (pinfunction "C2-_4") (pintype "passive"))
    )
    (net (code "70") (name "Net-(U31-FC0)") (class "Default")
      (node (ref "R338") (pin "1") (pinfunction "1_1") (pintype "passive"))
      (node (ref "U31") (pin "7") (pinfunction "FC1_7") (pintype "passive"))
      (node (ref "U31") (pin "8") (pinfunction "FC0_8") (pintype "passive"))
    )
    (net (code "71") (name "Net-(U40-An)") (class "Default")
      (node (ref "R276") (pin "2") (pinfunction "2_2") (pintype "passive"))
      (node (ref "U40") (pin "1") (pinfunction "An_1") (pintype "passive"))
    )
    (net (code "72") (name "Net-(VR5-Wiper)") (class "Default")
      (node (ref "R221") (pin "1") (pinfunction "1_1") (pintype "passive"))
      (node (ref "VR5") (pin "2") (pinfunction "Wiper_2") (pintype "passive"))
    )
    (net (code "73") (name "Net-(VR6-CCW)") (class "Default")
      (node (ref "R232") (pin "1") (pinfunction "1_1") (pintype "passive"))
      (node (ref "VR6") (pin "1") (pinfunction "CCW_1") (pintype "passive"))
      (node (ref "VR6") (pin "2") (pinfunction "Wiper_2") (pintype "passive"))
    )
    (net (code "74") (name "Net-(VR7-CCW)") (class "Default")
      (node (ref "R234") (pin "1") (pinfunction "1_1") (pintype "passive"))
      (node (ref "VR7") (pin "1") (pinfunction "CCW_1") (pintype "passive"))
      (node (ref "VR7") (pin "2") (pinfunction "Wiper_2") (pintype "passive"))
    )
    (net (code "75") (name "Net-(VR8-Wiper)") (class "Default")
      (node (ref "R250") (pin "1") (pinfunction "1_1") (pintype "passive"))
      (node (ref "VR8") (pin "2") (pinfunction "Wiper_2") (pintype "passive"))
    )
    (net (code "76") (name "unconnected-(J37-Pad13)") (class "Default")
      (node (ref "J37") (pin "13") (pinfunction "13_13") (pintype "passive+no_connect"))
    )
    (net (code "77") (name "unconnected-(J37-Pad21)") (class "Default")
      (node (ref "J37") (pin "21") (pinfunction "21_21") (pintype "passive+no_connect"))
    )
    (net (code "78") (name "unconnected-(J37-Pad22)") (class "Default")
      (node (ref "J37") (pin "22") (pinfunction "22_22") (pintype "passive+no_connect"))
    )
    (net (code "79") (name "unconnected-(J37-Pad23)") (class "Default")
      (node (ref "J37") (pin "23") (pinfunction "23_23") (pintype "passive+no_connect"))
    )
    (net (code "80") (name "unconnected-(J37-Pad24)") (class "Default")
      (node (ref "J37") (pin "24") (pinfunction "24_24") (pintype "passive+no_connect"))
    )
    (net (code "81") (name "unconnected-(J37-Pad25)") (class "Default")
      (node (ref "J37") (pin "25") (pinfunction "25_25") (pintype "passive+no_connect"))
    )
    (net (code "82") (name "unconnected-(J37-Pad29)") (class "Default")
      (node (ref "J37") (pin "29") (pinfunction "29_29") (pintype "passive+no_connect"))
    )
    (net (code "83") (name "unconnected-(J37-Pad38)") (class "Default")
      (node (ref "J37") (pin "38") (pinfunction "38_38") (pintype "passive+no_connect"))
    )
    (net (code "84") (name "unconnected-(J37-Pad39)") (class "Default")
      (node (ref "J37") (pin "39") (pinfunction "39_39") (pintype "passive+no_connect"))
    )
    (net (code "85") (name "unconnected-(J37-Pad40)") (class "Default")
      (node (ref "J37") (pin "40") (pinfunction "40_40") (pintype "passive+no_connect"))
    )
    (net (code "86") (name "unconnected-(J37-Pad42)") (class "Default")
      (node (ref "J37") (pin "42") (pinfunction "42_42") (pintype "passive+no_connect"))
    )
    (net (code "87") (name "unconnected-(J37-Pad43)") (class "Default")
      (node (ref "J37") (pin "43") (pinfunction "43_43") (pintype "passive+no_connect"))
    )
    (net (code "88") (name "unconnected-(J37-Pad44)") (class "Default")
      (node (ref "J37") (pin "44") (pinfunction "44_44") (pintype "passive+no_connect"))
    )
    (net (code "89") (name "unconnected-(J37-Pad45)") (class "Default")
      (node (ref "J37") (pin "45") (pinfunction "45_45") (pintype "passive+no_connect"))
    )
    (net (code "90") (name "unconnected-(J37-Pad46)") (class "Default")
      (node (ref "J37") (pin "46") (pinfunction "46_46") (pintype "passive+no_connect"))
    )
    (net (code "91") (name "unconnected-(J38-Pad1)") (class "Default")
      (node (ref "J38") (pin "1") (pinfunction "1_1") (pintype "passive+no_connect"))
    )
    (net (code "92") (name "unconnected-(J38-Pad14)") (class "Default")
      (node (ref "J38") (pin "14") (pinfunction "14_14") (pintype "passive+no_connect"))
    )
    (net (code "93") (name "unconnected-(J38-Pad29)") (class "Default")
      (node (ref "J38") (pin "29") (pinfunction "29_29") (pintype "passive+no_connect"))
    )
    (net (code "94") (name "unconnected-(J38-Pad33)") (class "Default")
      (node (ref "J38") (pin "33") (pinfunction "33_33") (pintype "passive+no_connect"))
    )
    (net (code "95") (name "unconnected-(J38-Pad34)") (class "Default")
      (node (ref "J38") (pin "34") (pinfunction "34_34") (pintype "passive+no_connect"))
    )
    (net (code "96") (name "unconnected-(J38-Pad35)") (class "Default")
      (node (ref "J38") (pin "35") (pinfunction "35_35") (pintype "passive+no_connect"))
    )
    (net (code "97") (name "unconnected-(J38-Pad36)") (class "Default")
      (node (ref "J38") (pin "36") (pinfunction "36_36") (pintype "passive+no_connect"))
    )
    (net (code "98") (name "unconnected-(J38-Pad37)") (class "Default")
      (node (ref "J38") (pin "37") (pinfunction "37_37") (pintype "passive+no_connect"))
    )
    (net (code "99") (name "unconnected-(J38-Pad38)") (class "Default")
      (node (ref "J38") (pin "38") (pinfunction "38_38") (pintype "passive+no_connect"))
    )
    (net (code "100") (name "unconnected-(J38-Pad39)") (class "Default")
      (node (ref "J38") (pin "39") (pinfunction "39_39") (pintype "passive+no_connect"))
    )
    (net (code "101") (name "unconnected-(J38-Pad42)") (class "Default")
      (node (ref "J38") (pin "42") (pinfunction "42_42") (pintype "passive+no_connect"))
    )
    (net (code "102") (name "unconnected-(J38-Pad44)") (class "Default")
      (node (ref "J38") (pin "44") (pinfunction "44_44") (pintype "passive+no_connect"))
    )
    (net (code "103") (name "unconnected-(J38-Pad45)") (class "Default")
      (node (ref "J38") (pin "45") (pinfunction "45_45") (pintype "passive+no_connect"))
    )
    (net (code "104") (name "unconnected-(J38-Pad46)") (class "Default")
      (node (ref "J38") (pin "46") (pinfunction "46_46") (pintype "passive+no_connect"))
    )
    (net (code "105") (name "unconnected-(U31-NC-Pad9)") (class "Default")
      (node (ref "U31") (pin "9") (pinfunction "NC_9") (pintype "passive+no_connect"))
    )
    (net (code "106") (name "unconnected-(U31-NC-Pad10)") (class "Default")
      (node (ref "U31") (pin "10") (pinfunction "NC_10") (pintype "passive+no_connect"))
    )
    (net (code "107") (name "unconnected-(U31-NC-Pad13)") (class "Default")
      (node (ref "U31") (pin "13") (pinfunction "NC_13") (pintype "passive+no_connect"))
    )
    (net (code "108") (name "unconnected-(U31-NC-Pad14)") (class "Default")
      (node (ref "U31") (pin "14") (pinfunction "NC_14") (pintype "passive+no_connect"))
    )
  )
)
